# 20140624_empf_nger_567_fr_se_v2.net
KiCad netlist of a schematic drawn in EAGLE
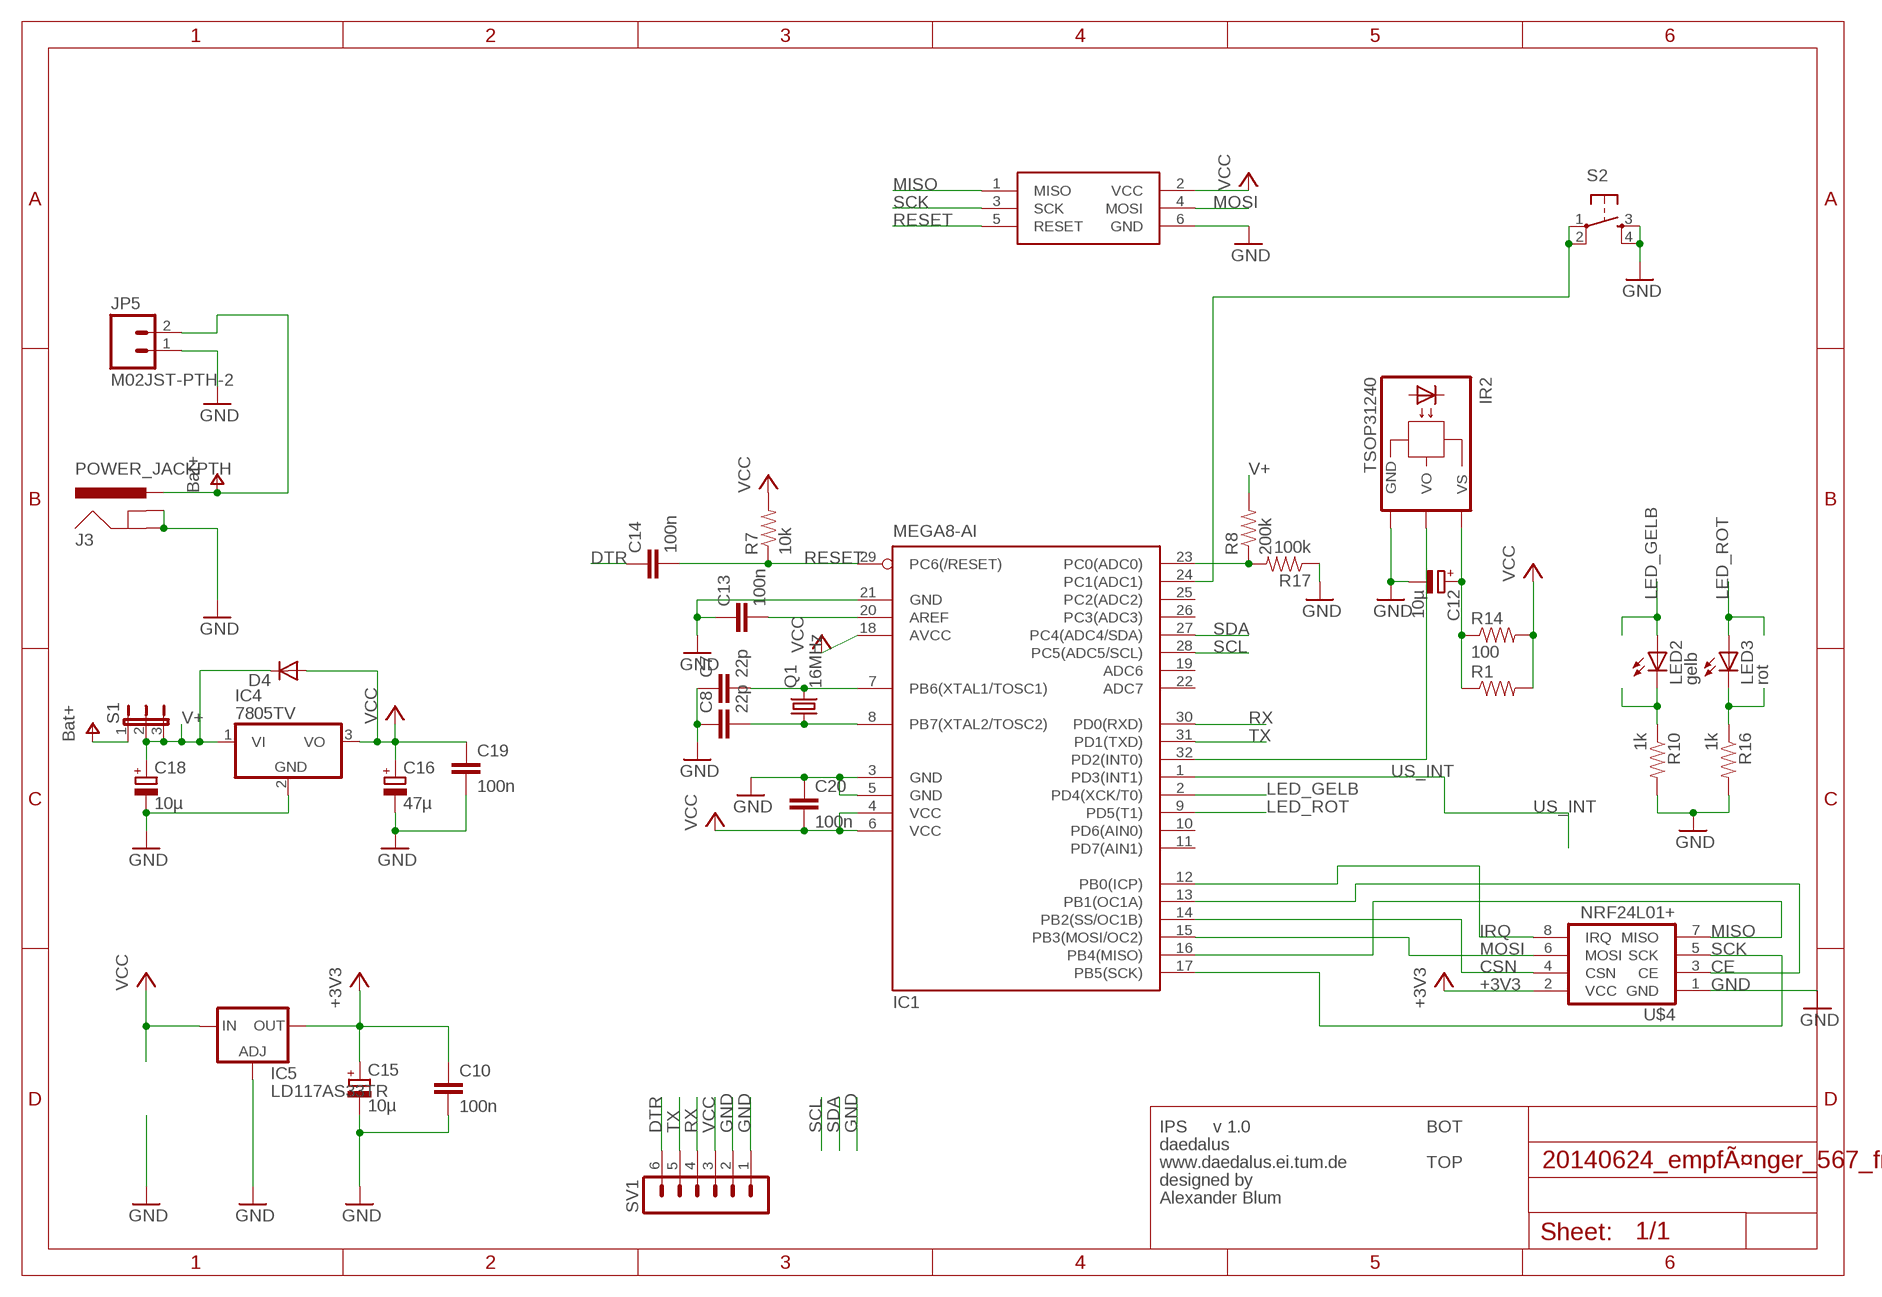
[diagram p0: schematic, sheet 1, part 1 of 2]
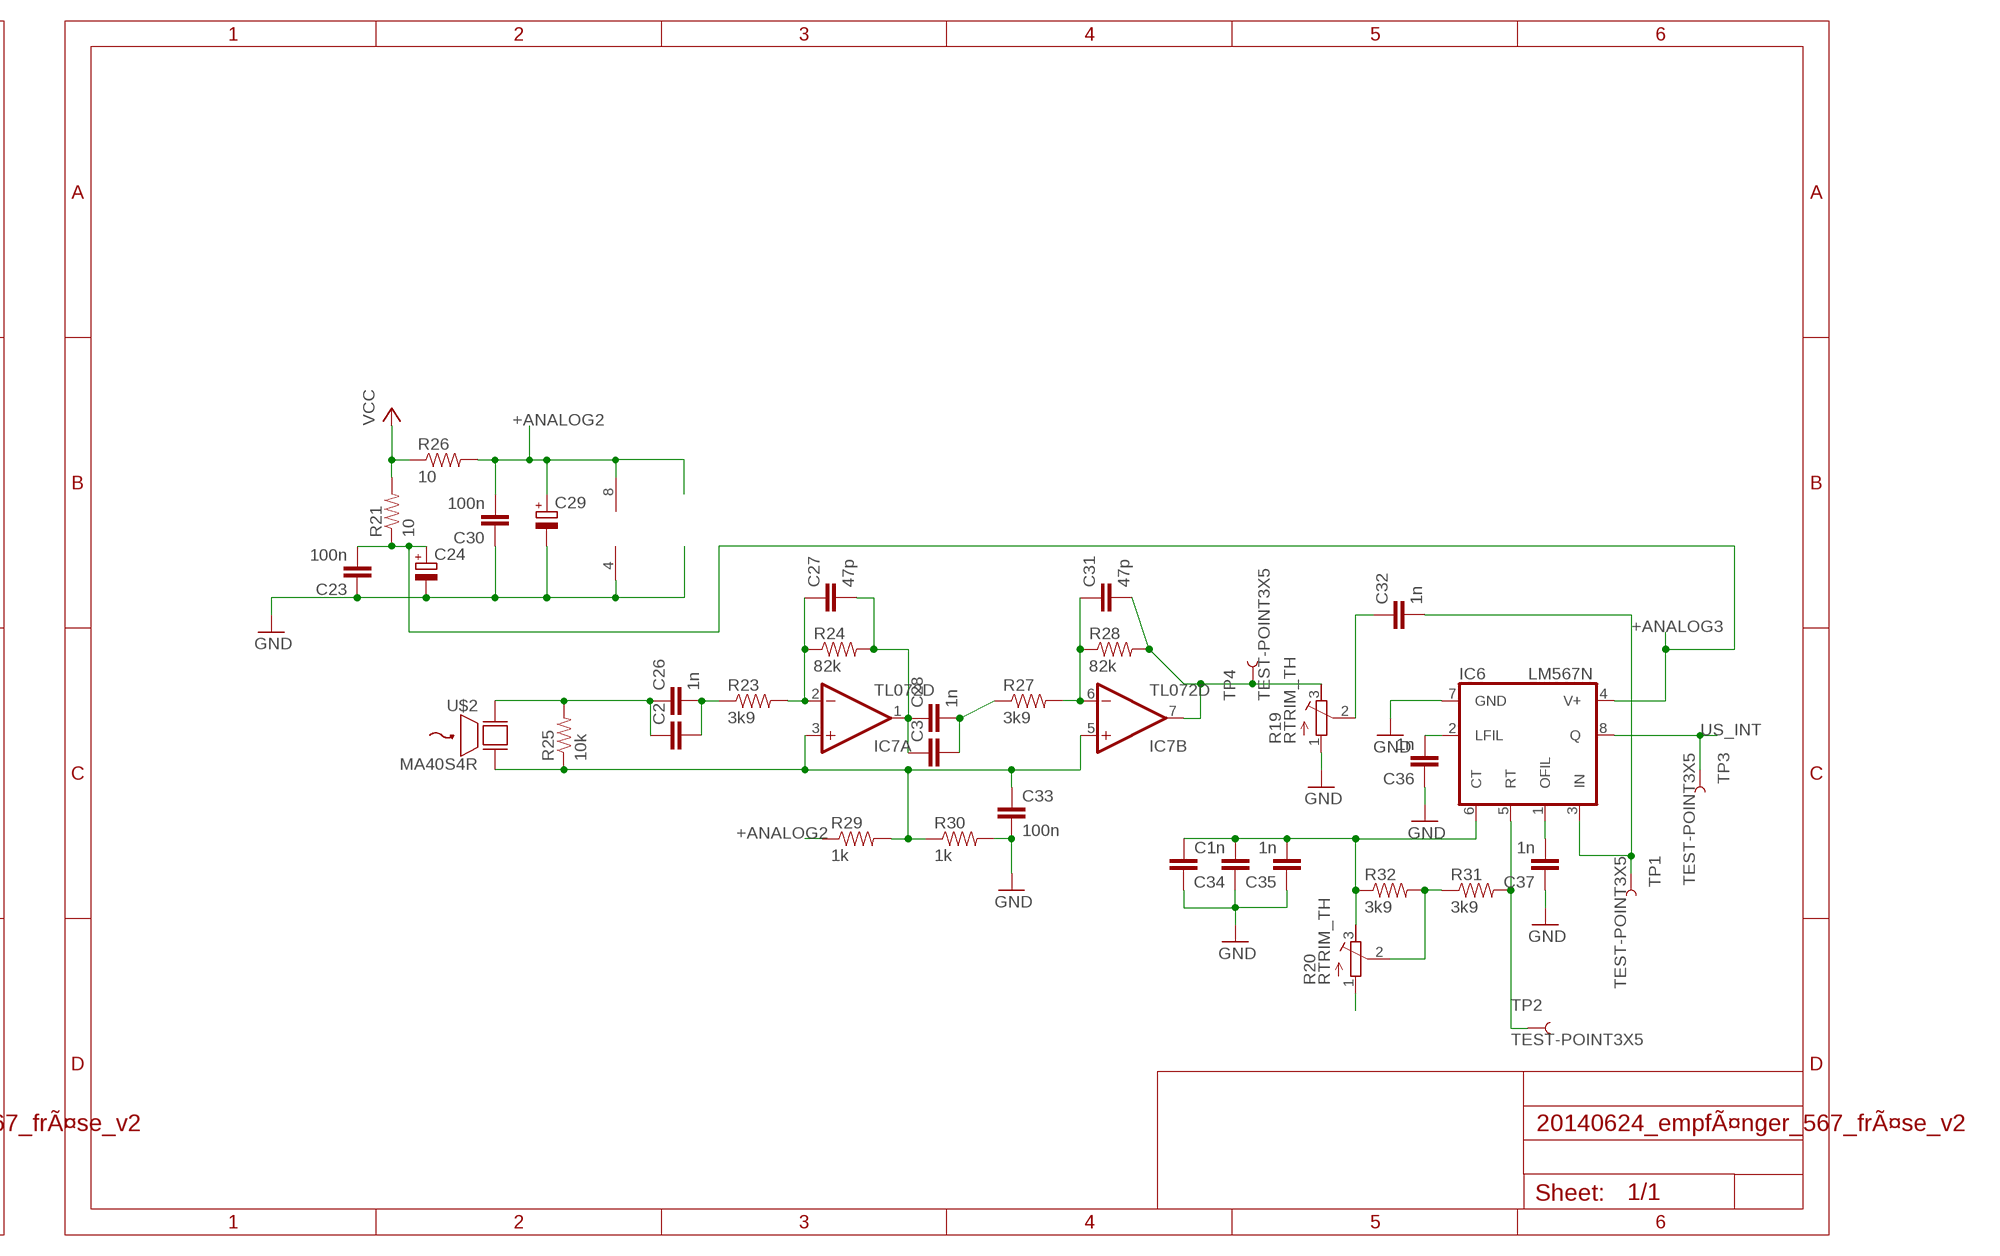
[diagram p1: schematic, sheet 1, part 2 of 2]

(export (version "E")
  (design (tool "Eeschema 10.0.6"))
  (components
    (comp (ref "C1")
      (value "CAP1206")
      (footprint "eagle-import:1206")
      (libsource (lib "eagle-import") (part "CAP1206"))
    )
    (comp (ref "C2")
      (value "CAP1206")
      (footprint "eagle-import:1206")
      (libsource (lib "eagle-import") (part "CAP1206"))
    )
    (comp (ref "C3")
      (value "CAP1206")
      (footprint "eagle-import:1206")
      (libsource (lib "eagle-import") (part "CAP1206"))
    )
    (comp (ref "C7")
      (value "22p")
      (footprint "eagle-import:0805")
      (libsource (lib "eagle-import") (part "CAP0805"))
    )
    (comp (ref "C8")
      (value "22p")
      (footprint "eagle-import:0805")
      (libsource (lib "eagle-import") (part "CAP0805"))
    )
    (comp (ref "C10")
      (value "100n")
      (footprint "eagle-import:0805")
      (libsource (lib "eagle-import") (part "CAP0805"))
    )
    (comp (ref "C12")
      (value "10µ")
      (footprint "eagle-import:E2,5-5")
      (libsource (lib "eagle-import") (part "CPOL-EUE2.5-5"))
    )
    (comp (ref "C13")
      (value "100n")
      (footprint "eagle-import:0805")
      (libsource (lib "eagle-import") (part "CAP0805"))
    )
    (comp (ref "C14")
      (value "100n")
      (footprint "eagle-import:0805")
      (libsource (lib "eagle-import") (part "CAP0805"))
    )
    (comp (ref "C15")
      (value "10µ")
      (footprint "eagle-import:E2,5-5")
      (libsource (lib "eagle-import") (part "CPOL-EUE2.5-5"))
    )
    (comp (ref "C16")
      (value "47µ")
      (footprint "eagle-import:E2,5-5")
      (libsource (lib "eagle-import") (part "CPOL-EUE2.5-5"))
    )
    (comp (ref "C18")
      (value "10µ")
      (footprint "eagle-import:E2,5-5")
      (libsource (lib "eagle-import") (part "CPOL-EUE2.5-5"))
    )
    (comp (ref "C19")
      (value "100n")
      (footprint "eagle-import:0805")
      (libsource (lib "eagle-import") (part "CAP0805"))
    )
    (comp (ref "C20")
      (value "100n")
      (footprint "eagle-import:0805")
      (libsource (lib "eagle-import") (part "CAP0805"))
    )
    (comp (ref "C23")
      (value "100n")
      (footprint "eagle-import:0805")
      (libsource (lib "eagle-import") (part "CAP0805"))
    )
    (comp (ref "C24")
      (value "CPOL-EUE2.5-5")
      (footprint "eagle-import:E2,5-5")
      (libsource (lib "eagle-import") (part "CPOL-EUE2.5-5"))
    )
    (comp (ref "C26")
      (value "1n")
      (footprint "eagle-import:0805")
      (libsource (lib "eagle-import") (part "CAP0805"))
    )
    (comp (ref "C27")
      (value "47p")
      (footprint "eagle-import:0805")
      (libsource (lib "eagle-import") (part "CAP0805"))
    )
    (comp (ref "C28")
      (value "1n")
      (footprint "eagle-import:0805")
      (libsource (lib "eagle-import") (part "CAP0805"))
    )
    (comp (ref "C29")
      (value "CPOL-EUE2.5-5")
      (footprint "eagle-import:E2,5-5")
      (libsource (lib "eagle-import") (part "CPOL-EUE2.5-5"))
    )
    (comp (ref "C30")
      (value "100n")
      (footprint "eagle-import:0805")
      (libsource (lib "eagle-import") (part "CAP0805"))
    )
    (comp (ref "C31")
      (value "47p")
      (footprint "eagle-import:0805")
      (libsource (lib "eagle-import") (part "CAP0805"))
    )
    (comp (ref "C32")
      (value "1n")
      (footprint "eagle-import:0805")
      (libsource (lib "eagle-import") (part "CAP0805"))
    )
    (comp (ref "C33")
      (value "100n")
      (footprint "eagle-import:0805")
      (libsource (lib "eagle-import") (part "CAP0805"))
    )
    (comp (ref "C34")
      (value "1n")
      (footprint "eagle-import:0805")
      (libsource (lib "eagle-import") (part "CAP0805"))
    )
    (comp (ref "C35")
      (value "1n")
      (footprint "eagle-import:0805")
      (libsource (lib "eagle-import") (part "CAP0805"))
    )
    (comp (ref "C36")
      (value "1n")
      (footprint "eagle-import:0805")
      (libsource (lib "eagle-import") (part "CAP0805"))
    )
    (comp (ref "C37")
      (value "1n")
      (footprint "eagle-import:0805")
      (libsource (lib "eagle-import") (part "CAP0805"))
    )
    (comp (ref "D4")
      (value "DIODE-MINIMELF")
      (footprint "eagle-import:MINIMELF")
      (libsource (lib "eagle-import") (part "DIODE-MINIMELF"))
    )
    (comp (ref "IC1")
      (value "MEGA8-AI")
      (footprint "eagle-import:TQFP32-08")
      (fields (field (name "MPN") "ATMEGA8-16AU"))
      (libsource (lib "eagle-import") (part "MEGA8-AI"))
    )
    (comp (ref "IC4")
      (value "7805TV")
      (footprint "eagle-import:TO220V")
      (libsource (lib "eagle-import") (part "78TV05"))
    )
    (comp (ref "IC5")
      (value "LD117AS33TR")
      (footprint "eagle-import:SOT223")
      (libsource (lib "eagle-import") (part "LD117A?S33TR"))
    )
    (comp (ref "IC6")
      (value "LM567N")
      (footprint "eagle-import:DIL08")
      (libsource (lib "eagle-import") (part "567NLM"))
    )
    (comp (ref "IC7")
      (value "TL072D")
      (footprint "eagle-import:SO08")
      (libsource (lib "eagle-import") (part "TL072D"))
    )
    (comp (ref "IR2")
      (value "TSOP31240")
      (footprint "eagle-import:TSOP31240")
      (libsource (lib "eagle-import") (part "TSOP31240"))
    )
    (comp (ref "J3")
      (value "POWER_JACKPTH")
      (footprint "eagle-import:POWER_JACK_PTH")
      (libsource (lib "eagle-import") (part "POWER_JACKPTH"))
    )
    (comp (ref "JP5")
      (value "M02JST-PTH-2")
      (footprint "eagle-import:JST-2-PTH")
      (libsource (lib "eagle-import") (part "M02JST-PTH-2"))
    )
    (comp (ref "LED2")
      (value "gelb")
      (footprint "eagle-import:LED5MM")
      (libsource (lib "eagle-import") (part "LED5MM"))
    )
    (comp (ref "LED3")
      (value "rot")
      (footprint "eagle-import:LED5MM")
      (libsource (lib "eagle-import") (part "LED5MM"))
    )
    (comp (ref "Q1")
      (value "16MHz")
      (footprint "eagle-import:HC49_S")
      (libsource (lib "eagle-import") (part "CRYSTALHC49S"))
    )
    (comp (ref "R1")
      (value "RESISTOR1206")
      (footprint "eagle-import:1206")
      (libsource (lib "eagle-import") (part "RESISTOR1206"))
    )
    (comp (ref "R7")
      (value "10k")
      (footprint "eagle-import:0805")
      (libsource (lib "eagle-import") (part "RESISTOR0805-RES"))
    )
    (comp (ref "R8")
      (value "200k")
      (footprint "eagle-import:0805")
      (libsource (lib "eagle-import") (part "RESISTOR0805-RES"))
    )
    (comp (ref "R10")
      (value "1k")
      (footprint "eagle-import:0805")
      (libsource (lib "eagle-import") (part "RESISTOR0805-RES"))
    )
    (comp (ref "R14")
      (value "100")
      (footprint "eagle-import:0805")
      (libsource (lib "eagle-import") (part "RESISTOR0805-RES"))
    )
    (comp (ref "R16")
      (value "1k")
      (footprint "eagle-import:0805")
      (libsource (lib "eagle-import") (part "RESISTOR0805-RES"))
    )
    (comp (ref "R17")
      (value "100k")
      (footprint "eagle-import:0805")
      (libsource (lib "eagle-import") (part "RESISTOR0805-RES"))
    )
    (comp (ref "R19")
      (value "RTRIM_TH")
      (footprint "eagle-import:RTRIM_TH")
      (libsource (lib "eagle-import") (part "RTRIM_TH"))
    )
    (comp (ref "R20")
      (value "RTRIM_TH")
      (footprint "eagle-import:RTRIM_TH")
      (libsource (lib "eagle-import") (part "RTRIM_TH"))
    )
    (comp (ref "R21")
      (value "10")
      (footprint "eagle-import:0805")
      (libsource (lib "eagle-import") (part "RESISTOR0805-RES"))
    )
    (comp (ref "R23")
      (value "3k9")
      (footprint "eagle-import:0805")
      (libsource (lib "eagle-import") (part "RESISTOR0805-RES"))
    )
    (comp (ref "R24")
      (value "82k")
      (footprint "eagle-import:0805")
      (libsource (lib "eagle-import") (part "RESISTOR0805-RES"))
    )
    (comp (ref "R25")
      (value "10k")
      (footprint "eagle-import:0805")
      (libsource (lib "eagle-import") (part "RESISTOR0805-RES"))
    )
    (comp (ref "R26")
      (value "10")
      (footprint "eagle-import:0805")
      (libsource (lib "eagle-import") (part "RESISTOR0805-RES"))
    )
    (comp (ref "R27")
      (value "3k9")
      (footprint "eagle-import:0805")
      (libsource (lib "eagle-import") (part "RESISTOR0805-RES"))
    )
    (comp (ref "R28")
      (value "82k")
      (footprint "eagle-import:0805")
      (libsource (lib "eagle-import") (part "RESISTOR0805-RES"))
    )
    (comp (ref "R29")
      (value "1k")
      (footprint "eagle-import:0805")
      (libsource (lib "eagle-import") (part "RESISTOR0805-RES"))
    )
    (comp (ref "R30")
      (value "1k")
      (footprint "eagle-import:0805")
      (libsource (lib "eagle-import") (part "RESISTOR0805-RES"))
    )
    (comp (ref "R31")
      (value "3k9")
      (footprint "eagle-import:0805")
      (libsource (lib "eagle-import") (part "RESISTOR0805-RES"))
    )
    (comp (ref "R32")
      (value "3k9")
      (footprint "eagle-import:0805")
      (libsource (lib "eagle-import") (part "RESISTOR0805-RES"))
    )
    (comp (ref "S1")
      (value "JP2E")
      (footprint "eagle-import:JP2")
      (libsource (lib "eagle-import") (part "JP2E"))
    )
    (comp (ref "S2")
      (value "TAC_SWITCHPTH")
      (footprint "eagle-import:TACTILE-PTH")
      (libsource (lib "eagle-import") (part "TAC_SWITCHPTH"))
    )
    (comp (ref "SV1")
      (value "MA06-1")
      (footprint "eagle-import:MA06-1")
      (libsource (lib "eagle-import") (part "MA06-1"))
    )
    (comp (ref "TP1")
      (value "TEST-POINT3X5")
      (footprint "eagle-import:PAD.03X.05")
      (libsource (lib "eagle-import") (part "TEST-POINT3X5"))
    )
    (comp (ref "TP2")
      (value "TEST-POINT3X5")
      (footprint "eagle-import:PAD.03X.05")
      (libsource (lib "eagle-import") (part "TEST-POINT3X5"))
    )
    (comp (ref "TP3")
      (value "TEST-POINT3X5")
      (footprint "eagle-import:PAD.03X.05")
      (libsource (lib "eagle-import") (part "TEST-POINT3X5"))
    )
    (comp (ref "TP4")
      (value "TEST-POINT3X5")
      (footprint "eagle-import:PAD.03X.05")
      (libsource (lib "eagle-import") (part "TEST-POINT3X5"))
    )
    (comp (ref "U$2")
      (value "MA40S4R")
      (footprint "eagle-import:MUS40")
      (libsource (lib "eagle-import") (part "MA40S4R"))
    )
    (comp (ref "U$3")
      (value "ISP_HEADER")
      (footprint "eagle-import:ISP_HEADER")
      (libsource (lib "eagle-import") (part "ISP_HEADER"))
    )
    (comp (ref "U$4")
      (value "NRF24L01+")
      (footprint "eagle-import:NRF24")
      (libsource (lib "eagle-import") (part "NRF24L01+"))
    )
  )
  (nets
    (net (code "1") (name "+3V3") (class "Default")
      (node (ref "C10") (pin "1") (pinfunction "1_1") (pintype "passive"))
      (node (ref "C15") (pin "+") (pinfunction "+_+") (pintype "passive"))
      (node (ref "IC5") (pin "4") (pinfunction "OUT_4") (pintype "passive"))
      (node (ref "U$4") (pin "2") (pinfunction "VCC_2") (pintype "power_in"))
    )
    (net (code "2") (name "/+ANALOG2") (class "Default")
      (node (ref "C29") (pin "+") (pinfunction "+_+") (pintype "passive"))
      (node (ref "C30") (pin "2") (pinfunction "2_2") (pintype "passive"))
      (node (ref "IC7") (pin "8") (pinfunction "V+_8") (pintype "power_in"))
      (node (ref "R26") (pin "2") (pinfunction "2_2") (pintype "passive"))
      (node (ref "R29") (pin "1") (pinfunction "1_1") (pintype "passive"))
    )
    (net (code "3") (name "/+ANALOG3") (class "Default")
      (node (ref "C23") (pin "2") (pinfunction "2_2") (pintype "passive"))
      (node (ref "C24") (pin "+") (pinfunction "+_+") (pintype "passive"))
      (node (ref "IC6") (pin "4") (pinfunction "V+_4") (pintype "power_in"))
      (node (ref "R21") (pin "1") (pinfunction "1_1") (pintype "passive"))
    )
    (net (code "4") (name "/CE") (class "Default")
      (node (ref "IC1") (pin "13") (pinfunction "PB1(OC1A)_13") (pintype "bidirectional"))
      (node (ref "U$4") (pin "3") (pinfunction "CE_3") (pintype "bidirectional"))
    )
    (net (code "5") (name "/CSN") (class "Default")
      (node (ref "IC1") (pin "14") (pinfunction "PB2(SS/OC1B)_14") (pintype "bidirectional"))
      (node (ref "U$4") (pin "4") (pinfunction "CSN_4") (pintype "bidirectional"))
    )
    (net (code "6") (name "/DTR") (class "Default")
      (node (ref "C14") (pin "1") (pinfunction "1_1") (pintype "passive"))
      (node (ref "SV1") (pin "6") (pinfunction "6_6") (pintype "passive"))
    )
    (net (code "7") (name "/IRQ") (class "Default")
      (node (ref "IC1") (pin "12") (pinfunction "PB0(ICP)_12") (pintype "bidirectional"))
      (node (ref "U$4") (pin "8") (pinfunction "IRQ_8") (pintype "bidirectional"))
    )
    (net (code "8") (name "/LED_GELB") (class "Default")
      (node (ref "IC1") (pin "2") (pinfunction "PD4(XCK/T0)_2") (pintype "bidirectional"))
      (node (ref "LED2") (pin "A") (pinfunction "A_A") (pintype "passive"))
    )
    (net (code "9") (name "/LED_ROT") (class "Default")
      (node (ref "IC1") (pin "9") (pinfunction "PD5(T1)_9") (pintype "bidirectional"))
      (node (ref "LED3") (pin "A") (pinfunction "A_A") (pintype "passive"))
    )
    (net (code "10") (name "/MISO") (class "Default")
      (node (ref "IC1") (pin "16") (pinfunction "PB4(MISO)_16") (pintype "bidirectional"))
      (node (ref "U$3") (pin "1") (pinfunction "MISO_1") (pintype "bidirectional"))
      (node (ref "U$4") (pin "7") (pinfunction "MISO_7") (pintype "bidirectional"))
    )
    (net (code "11") (name "/MOSI") (class "Default")
      (node (ref "IC1") (pin "15") (pinfunction "PB3(MOSI/OC2)_15") (pintype "bidirectional"))
      (node (ref "U$3") (pin "4") (pinfunction "MOSI_4") (pintype "bidirectional"))
      (node (ref "U$4") (pin "6") (pinfunction "MOSI_6") (pintype "bidirectional"))
    )
    (net (code "12") (name "/RESET") (class "Default")
      (node (ref "C14") (pin "2") (pinfunction "2_2") (pintype "passive"))
      (node (ref "IC1") (pin "29") (pinfunction "PC6(/RESET)_29") (pintype "bidirectional"))
      (node (ref "R7") (pin "1") (pinfunction "1_1") (pintype "passive"))
      (node (ref "U$3") (pin "5") (pinfunction "RESET_5") (pintype "bidirectional"))
    )
    (net (code "13") (name "/RX") (class "Default")
      (node (ref "IC1") (pin "30") (pinfunction "PD0(RXD)_30") (pintype "bidirectional"))
      (node (ref "SV1") (pin "4") (pinfunction "4_4") (pintype "passive"))
    )
    (net (code "14") (name "/SCK") (class "Default")
      (node (ref "IC1") (pin "17") (pinfunction "PB5(SCK)_17") (pintype "bidirectional"))
      (node (ref "U$3") (pin "3") (pinfunction "SCK_3") (pintype "bidirectional"))
      (node (ref "U$4") (pin "5") (pinfunction "SCK_5") (pintype "bidirectional"))
    )
    (net (code "15") (name "/SCL") (class "Default")
      (node (ref "IC1") (pin "28") (pinfunction "PC5(ADC5/SCL)_28") (pintype "bidirectional"))
    )
    (net (code "16") (name "/SDA") (class "Default")
      (node (ref "IC1") (pin "27") (pinfunction "PC4(ADC4/SDA)_27") (pintype "bidirectional"))
    )
    (net (code "17") (name "/TX") (class "Default")
      (node (ref "IC1") (pin "31") (pinfunction "PD1(TXD)_31") (pintype "bidirectional"))
      (node (ref "SV1") (pin "5") (pinfunction "5_5") (pintype "passive"))
    )
    (net (code "18") (name "/US_INT") (class "Default")
      (node (ref "IC1") (pin "1") (pinfunction "PD3(INT1)_1") (pintype "bidirectional"))
      (node (ref "IC6") (pin "8") (pinfunction "Q_8") (pintype "output"))
      (node (ref "TP3") (pin "P$1") (pinfunction "1_P$1") (pintype "bidirectional"))
    )
    (net (code "19") (name "/V+") (class "Default")
      (node (ref "C18") (pin "+") (pinfunction "+_+") (pintype "passive"))
      (node (ref "D4") (pin "C") (pinfunction "C_C") (pintype "passive"))
      (node (ref "IC4") (pin "1") (pinfunction "VI_1") (pintype "input"))
      (node (ref "R8") (pin "2") (pinfunction "2_2") (pintype "passive"))
      (node (ref "S1") (pin "2") (pinfunction "2_2") (pintype "passive"))
      (node (ref "S1") (pin "3") (pinfunction "3_3") (pintype "passive"))
    )
    (net (code "20") (name "Bat+") (class "Default")
      (node (ref "J3") (pin "PWR") (pinfunction "PWR_PWR") (pintype "bidirectional"))
      (node (ref "JP5") (pin "2") (pinfunction "2_2") (pintype "passive"))
      (node (ref "S1") (pin "1") (pinfunction "1_1") (pintype "passive"))
    )
    (net (code "21") (name "GND") (class "Default")
      (node (ref "C1") (pin "2") (pinfunction "2_2") (pintype "passive"))
      (node (ref "C10") (pin "2") (pinfunction "2_2") (pintype "passive"))
      (node (ref "C12") (pin "-") (pinfunction "-_-") (pintype "passive"))
      (node (ref "C13") (pin "1") (pinfunction "1_1") (pintype "passive"))
      (node (ref "C15") (pin "-") (pinfunction "-_-") (pintype "passive"))
      (node (ref "C16") (pin "-") (pinfunction "-_-") (pintype "passive"))
      (node (ref "C18") (pin "-") (pinfunction "-_-") (pintype "passive"))
      (node (ref "C19") (pin "2") (pinfunction "2_2") (pintype "passive"))
      (node (ref "C20") (pin "1") (pinfunction "1_1") (pintype "passive"))
      (node (ref "C23") (pin "1") (pinfunction "1_1") (pintype "passive"))
      (node (ref "C24") (pin "-") (pinfunction "-_-") (pintype "passive"))
      (node (ref "C29") (pin "-") (pinfunction "-_-") (pintype "passive"))
      (node (ref "C30") (pin "1") (pinfunction "1_1") (pintype "passive"))
      (node (ref "C33") (pin "2") (pinfunction "2_2") (pintype "passive"))
      (node (ref "C34") (pin "1") (pinfunction "1_1") (pintype "passive"))
      (node (ref "C35") (pin "1") (pinfunction "1_1") (pintype "passive"))
      (node (ref "C36") (pin "1") (pinfunction "1_1") (pintype "passive"))
      (node (ref "C37") (pin "1") (pinfunction "1_1") (pintype "passive"))
      (node (ref "C7") (pin "1") (pinfunction "1_1") (pintype "passive"))
      (node (ref "C8") (pin "1") (pinfunction "1_1") (pintype "passive"))
      (node (ref "IC1") (pin "21") (pinfunction "GND_21") (pintype "power_in"))
      (node (ref "IC1") (pin "3") (pinfunction "GND_3") (pintype "power_in"))
      (node (ref "IC1") (pin "5") (pinfunction "GND_5") (pintype "power_in"))
      (node (ref "IC4") (pin "2") (pinfunction "GND_2") (pintype "passive"))
      (node (ref "IC5") (pin "1") (pinfunction "ADJ_1") (pintype "input"))
      (node (ref "IC6") (pin "7") (pinfunction "GND_7") (pintype "power_in"))
      (node (ref "IC7") (pin "4") (pinfunction "V-_4") (pintype "power_in"))
      (node (ref "IR2") (pin "GND") (pinfunction "GND_GND") (pintype "power_in"))
      (node (ref "J3") (pin "GND") (pinfunction "GND_GND") (pintype "bidirectional"))
      (node (ref "J3") (pin "GNDBREAK") (pinfunction "GNDBREAK_GNDBREAK") (pintype "bidirectional"))
      (node (ref "JP5") (pin "1") (pinfunction "1_1") (pintype "passive"))
      (node (ref "R10") (pin "2") (pinfunction "2_2") (pintype "passive"))
      (node (ref "R16") (pin "2") (pinfunction "2_2") (pintype "passive"))
      (node (ref "R17") (pin "1") (pinfunction "1_1") (pintype "passive"))
      (node (ref "R19") (pin "1") (pinfunction "E_1") (pintype "passive"))
      (node (ref "R30") (pin "2") (pinfunction "2_2") (pintype "passive"))
      (node (ref "S2") (pin "3") (pinfunction "3_3") (pintype "passive"))
      (node (ref "S2") (pin "4") (pinfunction "4_4") (pintype "passive"))
      (node (ref "SV1") (pin "1") (pinfunction "1_1") (pintype "passive"))
      (node (ref "SV1") (pin "2") (pinfunction "2_2") (pintype "passive"))
      (node (ref "U$3") (pin "6") (pinfunction "GND_6") (pintype "bidirectional"))
      (node (ref "U$4") (pin "1") (pinfunction "GND_1") (pintype "power_in"))
    )
    (net (code "22") (name "Net-(C2-Pad1)") (class "Default")
      (node (ref "C2") (pin "1") (pinfunction "1_1") (pintype "passive"))
      (node (ref "C26") (pin "1") (pinfunction "1_1") (pintype "passive"))
      (node (ref "R25") (pin "2") (pinfunction "2_2") (pintype "passive"))
      (node (ref "U$2") (pin "2") (pinfunction "2_2") (pintype "passive"))
    )
    (net (code "23") (name "Net-(C2-Pad2)") (class "Default")
      (node (ref "C2") (pin "2") (pinfunction "2_2") (pintype "passive"))
      (node (ref "C26") (pin "2") (pinfunction "2_2") (pintype "passive"))
      (node (ref "R23") (pin "1") (pinfunction "1_1") (pintype "passive"))
    )
    (net (code "24") (name "Net-(C12-Pad+)") (class "Default")
      (node (ref "C12") (pin "+") (pinfunction "+_+") (pintype "passive"))
      (node (ref "IR2") (pin "VS") (pinfunction "VS_VS") (pintype "power_in"))
      (node (ref "R1") (pin "1") (pinfunction "1_1") (pintype "passive"))
      (node (ref "R14") (pin "1") (pinfunction "1_1") (pintype "passive"))
    )
    (net (code "25") (name "Net-(C28-Pad2)") (class "Default")
      (node (ref "C28") (pin "2") (pinfunction "2_2") (pintype "passive"))
      (node (ref "C3") (pin "2") (pinfunction "2_2") (pintype "passive"))
      (node (ref "R27") (pin "1") (pinfunction "1_1") (pintype "passive"))
    )
    (net (code "26") (name "Net-(IC1-AREF)") (class "Default")
      (node (ref "C13") (pin "2") (pinfunction "2_2") (pintype "passive"))
      (node (ref "IC1") (pin "20") (pinfunction "AREF_20") (pintype "passive"))
    )
    (net (code "27") (name "Net-(IC1-PB6(XTAL1{slash}TOSC1))") (class "Default")
      (node (ref "C7") (pin "2") (pinfunction "2_2") (pintype "passive"))
      (node (ref "IC1") (pin "7") (pinfunction "PB6(XTAL1/TOSC1)_7") (pintype "bidirectional"))
      (node (ref "Q1") (pin "2") (pinfunction "2_2") (pintype "passive"))
    )
    (net (code "28") (name "Net-(IC1-PB7(XTAL2{slash}TOSC2))") (class "Default")
      (node (ref "C8") (pin "2") (pinfunction "2_2") (pintype "passive"))
      (node (ref "IC1") (pin "8") (pinfunction "PB7(XTAL2/TOSC2)_8") (pintype "bidirectional"))
      (node (ref "Q1") (pin "1") (pinfunction "1_1") (pintype "passive"))
    )
    (net (code "29") (name "Net-(IC1-PC0(ADC0))") (class "Default")
      (node (ref "IC1") (pin "23") (pinfunction "PC0(ADC0)_23") (pintype "bidirectional"))
      (node (ref "R17") (pin "2") (pinfunction "2_2") (pintype "passive"))
      (node (ref "R8") (pin "1") (pinfunction "1_1") (pintype "passive"))
    )
    (net (code "30") (name "Net-(IC1-PC1(ADC1))") (class "Default")
      (node (ref "IC1") (pin "24") (pinfunction "PC1(ADC1)_24") (pintype "bidirectional"))
      (node (ref "S2") (pin "1") (pinfunction "1_1") (pintype "passive"))
      (node (ref "S2") (pin "2") (pinfunction "2_2") (pintype "passive"))
    )
    (net (code "31") (name "Net-(IC1-PD2(INT0))") (class "Default")
      (node (ref "IC1") (pin "32") (pinfunction "PD2(INT0)_32") (pintype "bidirectional"))
      (node (ref "IR2") (pin "VO") (pinfunction "VO_VO") (pintype "open_collector"))
    )
    (net (code "32") (name "Net-(IC6-CT)") (class "Default")
      (node (ref "C1") (pin "1") (pinfunction "1_1") (pintype "passive"))
      (node (ref "C34") (pin "2") (pinfunction "2_2") (pintype "passive"))
      (node (ref "C35") (pin "2") (pinfunction "2_2") (pintype "passive"))
      (node (ref "IC6") (pin "6") (pinfunction "CT_6") (pintype "passive"))
      (node (ref "R20") (pin "3") (pinfunction "A_3") (pintype "passive"))
      (node (ref "R32") (pin "1") (pinfunction "1_1") (pintype "passive"))
    )
    (net (code "33") (name "Net-(IC6-IN)") (class "Default")
      (node (ref "C32") (pin "2") (pinfunction "2_2") (pintype "passive"))
      (node (ref "IC6") (pin "3") (pinfunction "IN_3") (pintype "input"))
      (node (ref "TP1") (pin "P$1") (pinfunction "1_P$1") (pintype "bidirectional"))
    )
    (net (code "34") (name "Net-(IC6-LFIL)") (class "Default")
      (node (ref "C36") (pin "2") (pinfunction "2_2") (pintype "passive"))
      (node (ref "IC6") (pin "2") (pinfunction "LFIL_2") (pintype "passive"))
    )
    (net (code "35") (name "Net-(IC6-OFIL)") (class "Default")
      (node (ref "C37") (pin "2") (pinfunction "2_2") (pintype "passive"))
      (node (ref "IC6") (pin "1") (pinfunction "OFIL_1") (pintype "output"))
    )
    (net (code "36") (name "Net-(IC6-RT)") (class "Default")
      (node (ref "IC6") (pin "5") (pinfunction "RT_5") (pintype "passive"))
      (node (ref "R31") (pin "2") (pinfunction "2_2") (pintype "passive"))
      (node (ref "TP2") (pin "P$1") (pinfunction "1_P$1") (pintype "bidirectional"))
    )
    (net (code "37") (name "Net-(IC7A-+IN)") (class "Default")
      (node (ref "C33") (pin "1") (pinfunction "1_1") (pintype "passive"))
      (node (ref "IC7") (pin "3") (pinfunction "+IN_3") (pintype "input"))
      (node (ref "IC7") (pin "5") (pinfunction "+IN_5") (pintype "input"))
      (node (ref "R25") (pin "1") (pinfunction "1_1") (pintype "passive"))
      (node (ref "R29") (pin "2") (pinfunction "2_2") (pintype "passive"))
      (node (ref "R30") (pin "1") (pinfunction "1_1") (pintype "passive"))
      (node (ref "U$2") (pin "1") (pinfunction "1_1") (pintype "passive"))
    )
    (net (code "38") (name "Net-(IC7A--IN)") (class "Default")
      (node (ref "C27") (pin "1") (pinfunction "1_1") (pintype "passive"))
      (node (ref "IC7") (pin "2") (pinfunction "-IN_2") (pintype "input"))
      (node (ref "R23") (pin "2") (pinfunction "2_2") (pintype "passive"))
      (node (ref "R24") (pin "1") (pinfunction "1_1") (pintype "passive"))
    )
    (net (code "39") (name "Net-(IC7A-OUT)") (class "Default")
      (node (ref "C27") (pin "2") (pinfunction "2_2") (pintype "passive"))
      (node (ref "C28") (pin "1") (pinfunction "1_1") (pintype "passive"))
      (node (ref "C3") (pin "1") (pinfunction "1_1") (pintype "passive"))
      (node (ref "IC7") (pin "1") (pinfunction "OUT_1") (pintype "output"))
      (node (ref "R24") (pin "2") (pinfunction "2_2") (pintype "passive"))
    )
    (net (code "40") (name "Net-(IC7B--IN)") (class "Default")
      (node (ref "C31") (pin "1") (pinfunction "1_1") (pintype "passive"))
      (node (ref "IC7") (pin "6") (pinfunction "-IN_6") (pintype "input"))
      (node (ref "R27") (pin "2") (pinfunction "2_2") (pintype "passive"))
      (node (ref "R28") (pin "1") (pinfunction "1_1") (pintype "passive"))
    )
    (net (code "41") (name "Net-(IC7B-OUT)") (class "Default")
      (node (ref "C31") (pin "2") (pinfunction "2_2") (pintype "passive"))
      (node (ref "IC7") (pin "7") (pinfunction "OUT_7") (pintype "output"))
      (node (ref "R19") (pin "3") (pinfunction "A_3") (pintype "passive"))
      (node (ref "R28") (pin "2") (pinfunction "2_2") (pintype "passive"))
      (node (ref "TP4") (pin "P$1") (pinfunction "1_P$1") (pintype "bidirectional"))
    )
    (net (code "42") (name "Net-(LED2-C)") (class "Default")
      (node (ref "LED2") (pin "K") (pinfunction "C_K") (pintype "passive"))
      (node (ref "R10") (pin "1") (pinfunction "1_1") (pintype "passive"))
    )
    (net (code "43") (name "Net-(LED3-C)") (class "Default")
      (node (ref "LED3") (pin "K") (pinfunction "C_K") (pintype "passive"))
      (node (ref "R16") (pin "1") (pinfunction "1_1") (pintype "passive"))
    )
    (net (code "44") (name "Net-(R19-S)") (class "Default")
      (node (ref "C32") (pin "1") (pinfunction "1_1") (pintype "passive"))
      (node (ref "R19") (pin "2") (pinfunction "S_2") (pintype "passive"))
    )
    (net (code "45") (name "Net-(R20-S)") (class "Default")
      (node (ref "R20") (pin "2") (pinfunction "S_2") (pintype "passive"))
      (node (ref "R31") (pin "1") (pinfunction "1_1") (pintype "passive"))
      (node (ref "R32") (pin "2") (pinfunction "2_2") (pintype "passive"))
    )
    (net (code "46") (name "VCC") (class "Default")
      (node (ref "C16") (pin "+") (pinfunction "+_+") (pintype "passive"))
      (node (ref "C19") (pin "1") (pinfunction "1_1") (pintype "passive"))
      (node (ref "C20") (pin "2") (pinfunction "2_2") (pintype "passive"))
      (node (ref "D4") (pin "A") (pinfunction "A_A") (pintype "passive"))
      (node (ref "IC1") (pin "18") (pinfunction "AVCC_18") (pintype "power_in"))
      (node (ref "IC1") (pin "4") (pinfunction "VCC_4") (pintype "power_in"))
      (node (ref "IC1") (pin "6") (pinfunction "VCC_6") (pintype "power_in"))
      (node (ref "IC4") (pin "3") (pinfunction "VO_3") (pintype "passive"))
      (node (ref "IC5") (pin "3") (pinfunction "IN_3") (pintype "input"))
      (node (ref "R1") (pin "2") (pinfunction "2_2") (pintype "passive"))
      (node (ref "R14") (pin "2") (pinfunction "2_2") (pintype "passive"))
      (node (ref "R21") (pin "2") (pinfunction "2_2") (pintype "passive"))
      (node (ref "R26") (pin "1") (pinfunction "1_1") (pintype "passive"))
      (node (ref "R7") (pin "2") (pinfunction "2_2") (pintype "passive"))
      (node (ref "SV1") (pin "3") (pinfunction "3_3") (pintype "passive"))
      (node (ref "U$3") (pin "2") (pinfunction "VCC_2") (pintype "bidirectional"))
    )
    (net (code "47") (name "unconnected-(IC1-ADC6-Pad19)") (class "Default")
      (node (ref "IC1") (pin "19") (pinfunction "ADC6_19") (pintype "bidirectional"))
    )
    (net (code "48") (name "unconnected-(IC1-ADC7-Pad22)") (class "Default")
      (node (ref "IC1") (pin "22") (pinfunction "ADC7_22") (pintype "bidirectional"))
    )
    (net (code "49") (name "unconnected-(IC1-PC2(ADC2)-Pad25)") (class "Default")
      (node (ref "IC1") (pin "25") (pinfunction "PC2(ADC2)_25") (pintype "bidirectional"))
    )
    (net (code "50") (name "unconnected-(IC1-PC3(ADC3)-Pad26)") (class "Default")
      (node (ref "IC1") (pin "26") (pinfunction "PC3(ADC3)_26") (pintype "bidirectional"))
    )
    (net (code "51") (name "unconnected-(IC1-PD6(AIN0)-Pad10)") (class "Default")
      (node (ref "IC1") (pin "10") (pinfunction "PD6(AIN0)_10") (pintype "bidirectional"))
    )
    (net (code "52") (name "unconnected-(IC1-PD7(AIN1)-Pad11)") (class "Default")
      (node (ref "IC1") (pin "11") (pinfunction "PD7(AIN1)_11") (pintype "bidirectional"))
    )
    (net (code "53") (name "unconnected-(R20-E-Pad1)") (class "Default")
      (node (ref "R20") (pin "1") (pinfunction "E_1") (pintype "passive"))
    )
  )
)
